# USB-TTL_Converter.net
KiCad netlist of a schematic drawn in Altium Designer
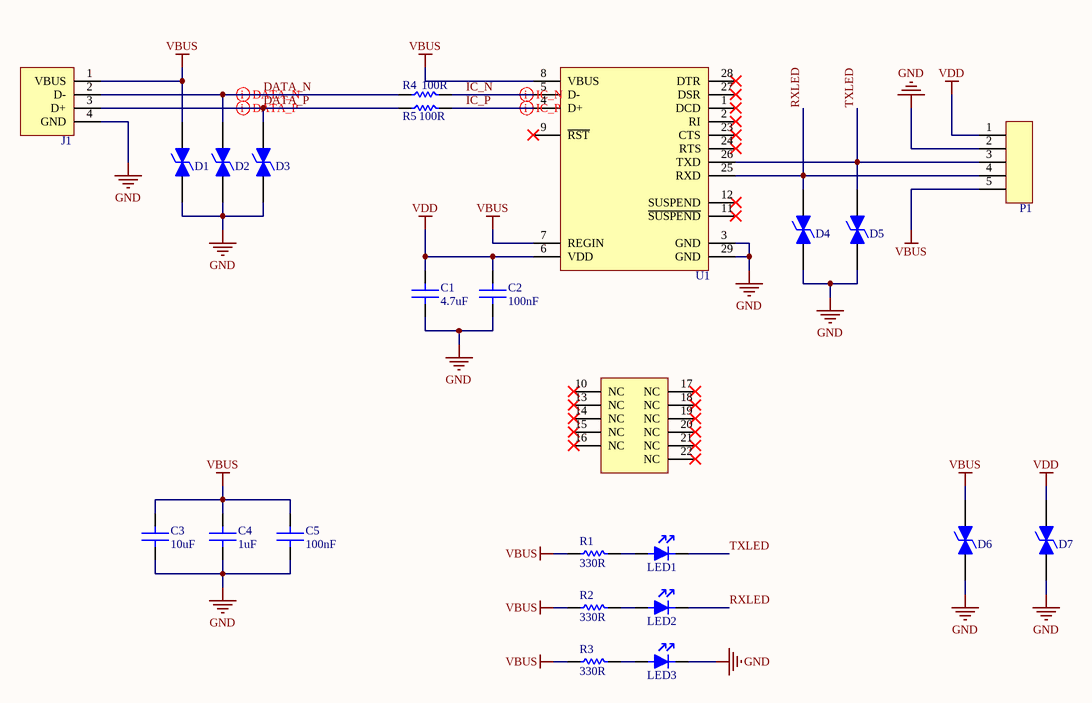
[diagram p0: USB-TTL Converter.SchDoc]

(export (version "E")
  (design (tool "Eeschema 10.0.6"))
  (components
    (comp (ref "C1")
      (value "4.7uF")
      (footprint "CAP 0402")
      (description "CAP CER 4.7UF 10V X5R 0402")
      (fields (field (name "Comment") "LMK105BBJ475MVLF"))
      (libsource (lib "USB-TTL Converter") (part "CAP CER 4.7UF 0402"))
    )
    (comp (ref "C2")
      (value "100nF")
      (footprint "CAP 0402")
      (description "CAP CER 0.1UF 16V X7R 0402")
      (fields (field (name "Comment") "C0402C104K4RACTU"))
      (libsource (lib "USB-TTL Converter") (part "CAP CER 100NF 0402"))
    )
    (comp (ref "C3")
      (value "10uF")
      (footprint "CAP 0603")
      (description "CAP CER 10UF 10V X5R 0603")
      (fields (field (name "Comment") "CL10A106MP8NNNC"))
      (libsource (lib "USB-TTL Converter") (part "CAP CER 10UF 0603"))
    )
    (comp (ref "C4")
      (value "1uF")
      (footprint "CAP 0402")
      (description "CAP CER 1UF 10V X5R 0402")
      (fields (field (name "Comment") "C0402X5R100-105MNE"))
      (libsource (lib "USB-TTL Converter") (part "CAP CER 1UF 0402"))
    )
    (comp (ref "C5")
      (value "100nF")
      (footprint "CAP 0402")
      (description "CAP CER 0.1UF 16V X7R 0402")
      (fields (field (name "Comment") "C0402C104K4RACTU"))
      (libsource (lib "USB-TTL Converter") (part "CAP CER 100NF 0402"))
    )
    (comp (ref "D1")
      (value "TPD1E10B06DPYR")
      (footprint "TVS DIODE")
      (description "TVS DIODE 5.5VWM 14VC 2X1SON")
      (libsource (lib "USB-TTL Converter") (part "TVS DIODE SMD"))
    )
    (comp (ref "D2")
      (value "TPD1E10B06DPYR")
      (footprint "TVS DIODE")
      (description "TVS DIODE 5.5VWM 14VC 2X1SON")
      (libsource (lib "USB-TTL Converter") (part "TVS DIODE SMD"))
    )
    (comp (ref "D3")
      (value "TPD1E10B06DPYR")
      (footprint "TVS DIODE")
      (description "TVS DIODE 5.5VWM 14VC 2X1SON")
      (libsource (lib "USB-TTL Converter") (part "TVS DIODE SMD"))
    )
    (comp (ref "D4")
      (value "TPD1E10B06DPYR")
      (footprint "TVS DIODE")
      (description "TVS DIODE 5.5VWM 14VC 2X1SON")
      (libsource (lib "USB-TTL Converter") (part "TVS DIODE SMD"))
    )
    (comp (ref "D5")
      (value "TPD1E10B06DPYR")
      (footprint "TVS DIODE")
      (description "TVS DIODE 5.5VWM 14VC 2X1SON")
      (libsource (lib "USB-TTL Converter") (part "TVS DIODE SMD"))
    )
    (comp (ref "D6")
      (value "TPD1E10B06DPYR")
      (footprint "TVS DIODE")
      (description "TVS DIODE 5.5VWM 14VC 2X1SON")
      (libsource (lib "USB-TTL Converter") (part "TVS DIODE SMD"))
    )
    (comp (ref "D7")
      (value "TPD1E10B06DPYR")
      (footprint "TVS DIODE")
      (description "TVS DIODE 5.5VWM 14VC 2X1SON")
      (libsource (lib "USB-TTL Converter") (part "TVS DIODE SMD"))
    )
    (comp (ref "J1")
      (value "629004113921")
      (footprint "USB TYPE-A")
      (description "CONN USB2.0 TYPEA 4P SMD RA")
      (libsource (lib "USB-TTL Converter") (part "CONN USB2.0 TYPE-A"))
    )
    (comp (ref "LED1")
      (value "150080VS75000")
      (footprint "LED 0805")
      (description "LED GREEN 0805 SMD")
      (libsource (lib "USB-TTL Converter") (part "GREEN LED 0805"))
    )
    (comp (ref "LED2")
      (value "150080VS75000")
      (footprint "LED 0805")
      (description "LED GREEN 0805 SMD")
      (libsource (lib "USB-TTL Converter") (part "GREEN LED 0805"))
    )
    (comp (ref "LED3")
      (value "150080VS75000")
      (footprint "LED 0805")
      (description "LED GREEN 0805 SMD")
      (libsource (lib "USB-TTL Converter") (part "RED LED 0805"))
    )
    (comp (ref "P1")
      (value "61300511021")
      (footprint "CONNECTOR")
      (description "CONN HEADER R/A 5POS 2.54MM")
      (libsource (lib "USB-TTL Converter") (part "CONN HEADER 5POS"))
    )
    (comp (ref "R1")
      (value "330R")
      (footprint "RES 0603")
      (description "RES 330 OHM 1% 1/5W 0603")
      (fields (field (name "Comment") "CRGH0603F330R"))
      (libsource (lib "USB-TTL Converter") (part "RES 330 OHM 0603"))
    )
    (comp (ref "R2")
      (value "330R")
      (footprint "RES 0603")
      (description "RES 330 OHM 1% 1/5W 0603")
      (fields (field (name "Comment") "CRGH0603F330R"))
      (libsource (lib "USB-TTL Converter") (part "RES 330 OHM 0603"))
    )
    (comp (ref "R3")
      (value "330R")
      (footprint "RES 0603")
      (description "RES 330 OHM 1% 1/5W 0603")
      (fields (field (name "Comment") "CRGH0603F330R"))
      (libsource (lib "USB-TTL Converter") (part "RES 330 OHM 0603"))
    )
    (comp (ref "R4")
      (value "100R")
      (footprint "RES 0603")
      (description "RES 100 OHM 1% 1/5W 0603")
      (fields (field (name "Comment") "RC0603FR-7W100RL"))
      (libsource (lib "USB-TTL Converter") (part "RES 100 OHM 0603"))
    )
    (comp (ref "R5")
      (value "100R")
      (footprint "RES 0603")
      (description "RES 100 OHM 1% 1/5W 0603")
      (fields (field (name "Comment") "RC0603FR-7W100RL"))
      (libsource (lib "USB-TTL Converter") (part "RES 100 OHM 0603"))
    )
    (comp (ref "U1")
      (value "CP2102-GM")
      (footprint "QFN-28")
      (description "IC USB-TO-UART BRIDGE 28VQFN")
      (libsource (lib "USB-TTL Converter") (part "CP2102 SMD"))
    )
  )
  (nets
    (net (code "1") (name "/DATA_N") (class "Default")
      (node (ref "D2") (pin "2") (pinfunction "2_2") (pintype "passive"))
      (node (ref "J1") (pin "2") (pinfunction "D-_2") (pintype "passive"))
      (node (ref "R4") (pin "1") (pinfunction "1_1") (pintype "passive"))
    )
    (net (code "2") (name "/DATA_P") (class "Default")
      (node (ref "D3") (pin "2") (pinfunction "2_2") (pintype "passive"))
      (node (ref "J1") (pin "3") (pinfunction "D+_3") (pintype "passive"))
      (node (ref "R5") (pin "1") (pinfunction "1_1") (pintype "passive"))
    )
    (net (code "3") (name "/IC_N") (class "Default")
      (node (ref "R4") (pin "2") (pinfunction "2_2") (pintype "passive"))
      (node (ref "U1") (pin "5") (pinfunction "D-_5") (pintype "passive"))
    )
    (net (code "4") (name "/IC_P") (class "Default")
      (node (ref "R5") (pin "2") (pinfunction "2_2") (pintype "passive"))
      (node (ref "U1") (pin "4") (pinfunction "D+_4") (pintype "passive"))
    )
    (net (code "5") (name "/RXLED") (class "Default")
      (node (ref "D4") (pin "2") (pinfunction "2_2") (pintype "passive"))
      (node (ref "LED2") (pin "2") (pintype "passive"))
      (node (ref "P1") (pin "4") (pinfunction "4_4") (pintype "passive"))
      (node (ref "U1") (pin "25") (pinfunction "RXD_25") (pintype "passive"))
    )
    (net (code "6") (name "/TXLED") (class "Default")
      (node (ref "D5") (pin "2") (pinfunction "2_2") (pintype "passive"))
      (node (ref "LED1") (pin "2") (pintype "passive"))
      (node (ref "P1") (pin "3") (pinfunction "3_3") (pintype "passive"))
      (node (ref "U1") (pin "26") (pinfunction "TXD_26") (pintype "passive"))
    )
    (net (code "7") (name "GND") (class "Default")
      (node (ref "C1") (pin "1") (pintype "passive"))
      (node (ref "C2") (pin "1") (pintype "passive"))
      (node (ref "C3") (pin "1") (pintype "passive"))
      (node (ref "C4") (pin "1") (pintype "passive"))
      (node (ref "C5") (pin "1") (pintype "passive"))
      (node (ref "D1") (pin "1") (pinfunction "1_1") (pintype "passive"))
      (node (ref "D2") (pin "1") (pinfunction "1_1") (pintype "passive"))
      (node (ref "D3") (pin "1") (pinfunction "1_1") (pintype "passive"))
      (node (ref "D4") (pin "1") (pinfunction "1_1") (pintype "passive"))
      (node (ref "D5") (pin "1") (pinfunction "1_1") (pintype "passive"))
      (node (ref "D6") (pin "1") (pinfunction "1_1") (pintype "passive"))
      (node (ref "D7") (pin "1") (pinfunction "1_1") (pintype "passive"))
      (node (ref "J1") (pin "4") (pinfunction "GND_4") (pintype "passive"))
      (node (ref "LED3") (pin "2") (pintype "passive"))
      (node (ref "P1") (pin "2") (pinfunction "2_2") (pintype "passive"))
      (node (ref "U1") (pin "29") (pinfunction "GND_29") (pintype "passive"))
      (node (ref "U1") (pin "3") (pinfunction "GND_3") (pintype "passive"))
    )
    (net (code "8") (name "Net-(LED1-Pad1)") (class "Default")
      (node (ref "LED1") (pin "1") (pintype "passive"))
      (node (ref "R1") (pin "2") (pinfunction "2_2") (pintype "passive"))
    )
    (net (code "9") (name "Net-(LED2-Pad1)") (class "Default")
      (node (ref "LED2") (pin "1") (pintype "passive"))
      (node (ref "R2") (pin "2") (pinfunction "2_2") (pintype "passive"))
    )
    (net (code "10") (name "Net-(LED3-Pad1)") (class "Default")
      (node (ref "LED3") (pin "1") (pintype "passive"))
      (node (ref "R3") (pin "2") (pinfunction "2_2") (pintype "passive"))
    )
    (net (code "11") (name "VBUS") (class "Default")
      (node (ref "C3") (pin "2") (pintype "passive"))
      (node (ref "C4") (pin "2") (pintype "passive"))
      (node (ref "C5") (pin "2") (pintype "passive"))
      (node (ref "D1") (pin "2") (pinfunction "2_2") (pintype "passive"))
      (node (ref "D6") (pin "2") (pinfunction "2_2") (pintype "passive"))
      (node (ref "J1") (pin "1") (pinfunction "VBUS_1") (pintype "passive"))
      (node (ref "P1") (pin "5") (pinfunction "5_5") (pintype "passive"))
      (node (ref "R1") (pin "1") (pinfunction "1_1") (pintype "passive"))
      (node (ref "R2") (pin "1") (pinfunction "1_1") (pintype "passive"))
      (node (ref "R3") (pin "1") (pinfunction "1_1") (pintype "passive"))
      (node (ref "U1") (pin "7") (pinfunction "REGIN_7") (pintype "passive"))
      (node (ref "U1") (pin "8") (pinfunction "VBUS_8") (pintype "passive"))
    )
    (net (code "12") (name "VDD") (class "Default")
      (node (ref "C1") (pin "2") (pintype "passive"))
      (node (ref "C2") (pin "2") (pintype "passive"))
      (node (ref "D7") (pin "2") (pinfunction "2_2") (pintype "passive"))
      (node (ref "P1") (pin "1") (pinfunction "1_1") (pintype "passive"))
      (node (ref "U1") (pin "6") (pinfunction "VDD_6") (pintype "passive"))
    )
    (net (code "13") (name "unconnected-(U1-CTS-Pad23)") (class "Default")
      (node (ref "U1") (pin "23") (pinfunction "CTS_23") (pintype "passive+no_connect"))
    )
    (net (code "14") (name "unconnected-(U1-DCD-Pad1)") (class "Default")
      (node (ref "U1") (pin "1") (pinfunction "DCD_1") (pintype "passive+no_connect"))
    )
    (net (code "15") (name "unconnected-(U1-DSR-Pad27)") (class "Default")
      (node (ref "U1") (pin "27") (pinfunction "DSR_27") (pintype "passive+no_connect"))
    )
    (net (code "16") (name "unconnected-(U1-DTR-Pad28)") (class "Default")
      (node (ref "U1") (pin "28") (pinfunction "DTR_28") (pintype "passive+no_connect"))
    )
    (net (code "17") (name "unconnected-(U1-NC-Pad10)") (class "Default")
      (node (ref "U1") (pin "10") (pinfunction "NC_10") (pintype "passive+no_connect"))
    )
    (net (code "18") (name "unconnected-(U1-NC-Pad13)") (class "Default")
      (node (ref "U1") (pin "13") (pinfunction "NC_13") (pintype "passive+no_connect"))
    )
    (net (code "19") (name "unconnected-(U1-NC-Pad14)") (class "Default")
      (node (ref "U1") (pin "14") (pinfunction "NC_14") (pintype "passive+no_connect"))
    )
    (net (code "20") (name "unconnected-(U1-NC-Pad15)") (class "Default")
      (node (ref "U1") (pin "15") (pinfunction "NC_15") (pintype "passive+no_connect"))
    )
    (net (code "21") (name "unconnected-(U1-NC-Pad16)") (class "Default")
      (node (ref "U1") (pin "16") (pinfunction "NC_16") (pintype "passive+no_connect"))
    )
    (net (code "22") (name "unconnected-(U1-NC-Pad17)") (class "Default")
      (node (ref "U1") (pin "17") (pinfunction "NC_17") (pintype "passive+no_connect"))
    )
    (net (code "23") (name "unconnected-(U1-NC-Pad18)") (class "Default")
      (node (ref "U1") (pin "18") (pinfunction "NC_18") (pintype "passive+no_connect"))
    )
    (net (code "24") (name "unconnected-(U1-NC-Pad19)") (class "Default")
      (node (ref "U1") (pin "19") (pinfunction "NC_19") (pintype "passive+no_connect"))
    )
    (net (code "25") (name "unconnected-(U1-NC-Pad20)") (class "Default")
      (node (ref "U1") (pin "20") (pinfunction "NC_20") (pintype "passive+no_connect"))
    )
    (net (code "26") (name "unconnected-(U1-NC-Pad21)") (class "Default")
      (node (ref "U1") (pin "21") (pinfunction "NC_21") (pintype "passive+no_connect"))
    )
    (net (code "27") (name "unconnected-(U1-NC-Pad22)") (class "Default")
      (node (ref "U1") (pin "22") (pinfunction "NC_22") (pintype "passive+no_connect"))
    )
    (net (code "28") (name "unconnected-(U1-RI-Pad2)") (class "Default")
      (node (ref "U1") (pin "2") (pinfunction "RI_2") (pintype "passive+no_connect"))
    )
    (net (code "29") (name "unconnected-(U1-RTS-Pad24)") (class "Default")
      (node (ref "U1") (pin "24") (pinfunction "RTS_24") (pintype "passive+no_connect"))
    )
    (net (code "30") (name "unconnected-(U1-SUSPEND-Pad12)") (class "Default")
      (node (ref "U1") (pin "12") (pinfunction "SUSPEND_12") (pintype "passive+no_connect"))
    )
    (net (code "31") (name "unconnected-(U1-~{RST}-Pad9)") (class "Default")
      (node (ref "U1") (pin "9") (pinfunction "~{RST}_9") (pintype "passive+no_connect"))
    )
    (net (code "32") (name "unconnected-(U1-~{SUSPEND}-Pad11)") (class "Default")
      (node (ref "U1") (pin "11") (pinfunction "~{SUSPEND}_11") (pintype "passive+no_connect"))
    )
  )
)
